# SEC_POWER.net
KiCad netlist of a schematic drawn in Altium Designer
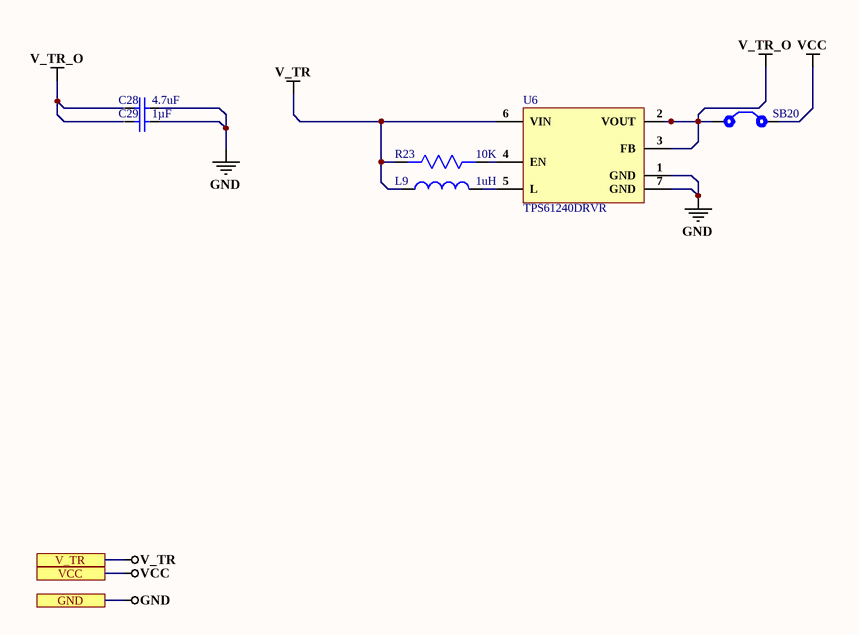
[diagram p0: SEC_POWER.SchDoc]

(export (version "E")
  (design (tool "Eeschema 10.0.6"))
  (components
    (comp (ref "C28")
      (value "4.7uF")
      (footprint "Cap0402")
      (description "CAP CER 4.7UF 6.3V X5R 0402")
      (fields
        (field (name "MANUFACTURER") "Yageo")
        (field (name "MANUFACTURER PART NUMBER") "CC0402MRX5R5BB475")
      )
      (libsource (lib "TT_IntLib") (part "CC0402MRX5R5BB475"))
    )
    (comp (ref "C29")
      (value "1µF")
      (footprint "Cap0402")
      (description "CAP CER 1UF 25V X5R 0402")
      (fields
        (field (name "MANUFACTURER") "Murata")
        (field (name "MANUFACTURER PART NUMBER") "GRM155R61E105KA12D")
      )
      (libsource (lib "TT_IntLib") (part "GRM155R61E105KA12D"))
    )
    (comp (ref "L9")
      (value "1uH")
      (footprint "IND 0603")
      (description "1uH ±20% 1A 180mΩ 0603 Inductors")
      (fields (field (name "MANUFACTURER") "microgate") (field (name "TOLERANCE") "±20%"))
      (libsource (lib "TT_IntLib") (part "MGFL1608F1R0MT-LF"))
    )
    (comp (ref "R23")
      (value "10K")
      (footprint "Res-0201")
      (description "RES SMD 10K OHM 1% 1/20W 0201")
      (fields
        (field (name "MANUFACTURER") "Yageo")
        (field (name "MANUFACTURER PART NUMBER") "RC0201FR-0710KL")
      )
      (libsource (lib "TT_IntLib") (part "RC0201FR-0710KL"))
    )
    (comp (ref "SB20")
      (value "Solder Bridge")
      (footprint "Solder Bridge")
      (description "Solder Bridge ON")
      (libsource (lib "TT_IntLib") (part "Solder Bridge"))
    )
    (comp (ref "U6")
      (value "TPS61240DRVR")
      (footprint "TPS61240DRVR")
      (description "IC REG BOOST SYNC 5V 0.45A 6SON")
      (fields (field (name "MANUFACTURER") "Texas Instruments"))
      (libsource (lib "TT_IntLib") (part "TPS61240DRVR"))
    )
  )
  (nets
    (net (code "1") (name "GND") (class "Default")
      (node (ref "C28") (pin "1") (pintype "passive"))
      (node (ref "C29") (pin "1") (pintype "passive"))
      (node (ref "U6") (pin "1") (pinfunction "GND_1") (pintype "passive"))
      (node (ref "U6") (pin "7") (pinfunction "GND_7") (pintype "passive"))
    )
    (net (code "2") (name "Net-(U6-EN)") (class "Default")
      (node (ref "R23") (pin "1") (pintype "passive"))
      (node (ref "U6") (pin "4") (pinfunction "EN_4") (pintype "passive"))
    )
    (net (code "3") (name "Net-(U6-L)") (class "Default")
      (node (ref "L9") (pin "2") (pinfunction "2_2") (pintype "passive"))
      (node (ref "U6") (pin "5") (pinfunction "L_5") (pintype "passive"))
    )
    (net (code "4") (name "VCC") (class "Default")
      (node (ref "SB20") (pin "2") (pinfunction "2_2") (pintype "passive"))
    )
    (net (code "5") (name "V_TR") (class "Default")
      (node (ref "L9") (pin "1") (pinfunction "1_1") (pintype "passive"))
      (node (ref "R23") (pin "2") (pintype "passive"))
      (node (ref "U6") (pin "6") (pinfunction "VIN_6") (pintype "passive"))
    )
    (net (code "6") (name "V_TR_O") (class "Default")
      (node (ref "SB20") (pin "1") (pinfunction "1_1") (pintype "passive"))
      (node (ref "U6") (pin "2") (pinfunction "VOUT_2") (pintype "passive"))
      (node (ref "U6") (pin "3") (pinfunction "FB_3") (pintype "passive"))
    )
    (net (code "7") (name "unconnected-(C28-Pad2)") (class "Default")
      (node (ref "C28") (pin "2") (pintype "passive"))
    )
    (net (code "8") (name "unconnected-(C29-Pad2)") (class "Default")
      (node (ref "C29") (pin "2") (pintype "passive"))
    )
  )
)
